# UCN_LV.net
KiCad netlist of a schematic drawn in Altium Designer
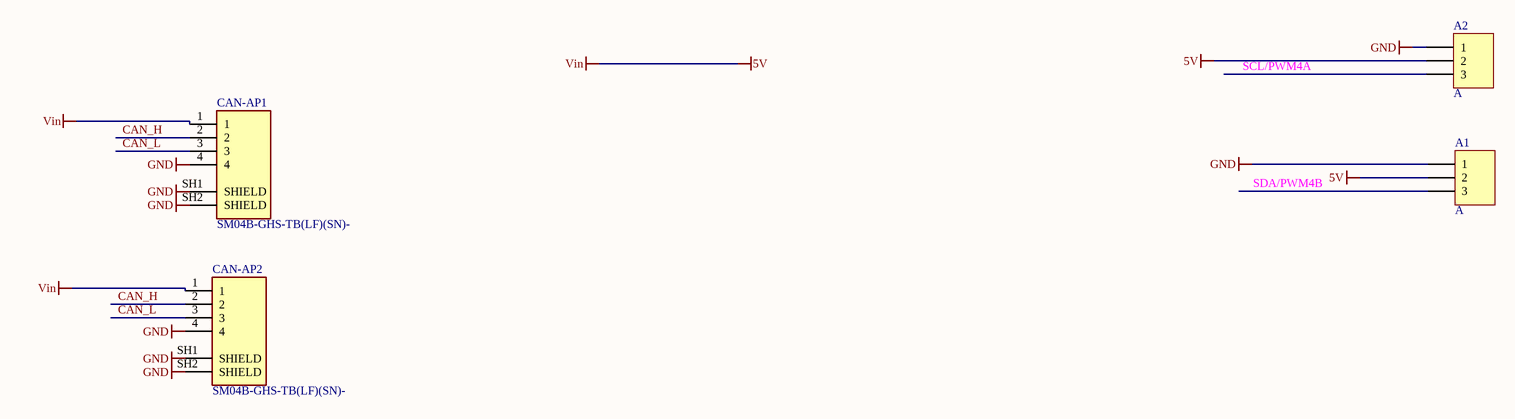
[diagram p0: UCN LV.SchDoc]

(export (version "E")
  (design (tool "Eeschema 10.0.6"))
  (components
    (comp (ref "A1")
      (value "A")
      (footprint "HDR Side 3 pin")
      (description "Header, 4-Pin")
      (fields (field (name "MF") "Connfly electronic (Zhenqin)") (field (name "MP") "PLS-3 (DS1021-1x3)"))
      (libsource (lib "DC_DC") (part "Header 3"))
    )
    (comp (ref "A2")
      (value "A")
      (footprint "HDR Side 3 pin")
      (description "Header, 4-Pin")
      (fields (field (name "MF") "Connfly electronic (Zhenqin)") (field (name "MP") "PLS-3 (DS1021-1x3)"))
      (libsource (lib "DC_DC") (part "Header 3"))
    )
    (comp (ref "CAN-AP1")
      (value "SM04B-GHS-TB(LF)(SN)-")
      (footprint "JST_SM04B-GHS-TB(LF)(SN)-")
      (description "Connector Header Surface Mount, Right Angle 4 position 0.049 _1.25mm_")
      (fields (field (name "MP") "SM04B-GHS-TB(LF)(SN)") (field (name "MF") "JST Sales"))
      (libsource (lib "lib") (part "SM04B-GHS-TB(LF)(SN)-"))
    )
    (comp (ref "CAN-AP2")
      (value "SM04B-GHS-TB(LF)(SN)-")
      (footprint "JST_SM04B-GHS-TB(LF)(SN)-")
      (description "Connector Header Surface Mount, Right Angle 4 position 0.049 _1.25mm_")
      (fields (field (name "MP") "SM04B-GHS-TB(LF)(SN)") (field (name "MF") "JST Sales"))
      (libsource (lib "lib") (part "SM04B-GHS-TB(LF)(SN)-"))
    )
  )
  (nets
    (net (code "1") (name "/CAN_H") (class "Default")
      (node (ref "CAN-AP1") (pin "2") (pinfunction "2_2") (pintype "passive"))
      (node (ref "CAN-AP2") (pin "2") (pinfunction "2_2") (pintype "passive"))
    )
    (net (code "2") (name "/CAN_L") (class "Default")
      (node (ref "CAN-AP1") (pin "3") (pinfunction "3_3") (pintype "passive"))
      (node (ref "CAN-AP2") (pin "3") (pinfunction "3_3") (pintype "passive"))
    )
    (net (code "3") (name "/SCL{slash}PWM4A") (class "Default")
      (node (ref "A2") (pin "3") (pinfunction "3_3") (pintype "passive"))
    )
    (net (code "4") (name "/SDA{slash}PWM4B") (class "Default")
      (node (ref "A1") (pin "3") (pinfunction "3_3") (pintype "passive"))
    )
    (net (code "5") (name "5V") (class "Default")
      (node (ref "A1") (pin "2") (pinfunction "2_2") (pintype "passive"))
      (node (ref "A2") (pin "2") (pinfunction "2_2") (pintype "passive"))
      (node (ref "CAN-AP1") (pin "1") (pinfunction "1_1") (pintype "passive"))
      (node (ref "CAN-AP2") (pin "1") (pinfunction "1_1") (pintype "passive"))
    )
    (net (code "6") (name "GND") (class "Default")
      (node (ref "A1") (pin "1") (pinfunction "1_1") (pintype "passive"))
      (node (ref "A2") (pin "1") (pinfunction "1_1") (pintype "passive"))
      (node (ref "CAN-AP1") (pin "4") (pinfunction "4_4") (pintype "passive"))
      (node (ref "CAN-AP1") (pin "SH1") (pinfunction "SHIELD_SH1") (pintype "power_in"))
      (node (ref "CAN-AP1") (pin "SH2") (pinfunction "SHIELD_SH2") (pintype "power_in"))
      (node (ref "CAN-AP2") (pin "4") (pinfunction "4_4") (pintype "passive"))
      (node (ref "CAN-AP2") (pin "SH1") (pinfunction "SHIELD_SH1") (pintype "power_in"))
      (node (ref "CAN-AP2") (pin "SH2") (pinfunction "SHIELD_SH2") (pintype "power_in"))
    )
  )
)
